# Battery.net
KiCad netlist of a schematic drawn in Altium Designer
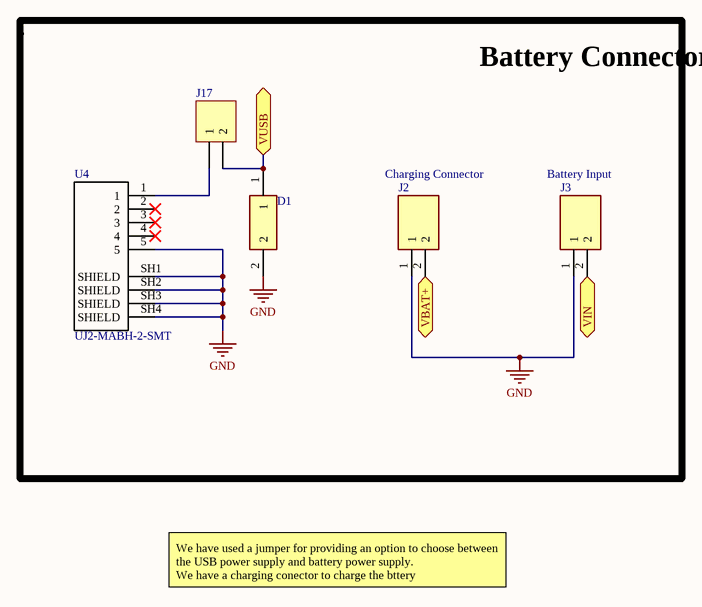
[diagram p0: Battery.SchDoc]

(export (version "E")
  (design (tool "Eeschema 10.0.6"))
  (components
    (comp (ref "D1")
      (value "TPD1E10B06DPYT")
      (footprint "Library_Cart:DPY(R-PX1SON-N2)")
      (description "TVS Diode (Bi-directional)")
      (fields (field (name "MOUSER PART NUMBER") "595-TPD1E10B06DPYT"))
      (libsource (lib "*") (part "TPD1E10B06DPYT"))
    )
    (comp (ref "J2")
      (value "282837-2")
      (footprint "SamacSys:SHDR2W100P0X508_1X2_1016X820X1030P")
      (description "Connector")
      (fields (field (name "MOUSER PART NUMBER") "571-2828372") (field (name "RS PART NUMBER") "7100100P"))
      (libsource (lib "*") (part "282837-2"))
    )
    (comp (ref "J3")
      (value "282837-2")
      (footprint "SamacSys:SHDR2W100P0X508_1X2_1016X820X1030P")
      (description "Connector")
      (fields (field (name "MOUSER PART NUMBER") "571-2828372") (field (name "RS PART NUMBER") "7100100P"))
      (libsource (lib "*") (part "282837-2"))
    )
    (comp (ref "J17")
      (value "Header 2")
      (footprint "HDR1X2")
      (description "Header, 2-Pin")
      (fields
        (field (name "MANUFACTURER_PART_NUMBER") "BG301-04-A-0540-L-B")
        (field (name "DIGI-KEY PART NUMBER") "2073-BG301-02-A-0540-L-BCT-ND")
      )
      (libsource (lib "Miscellaneous Connectors") (part "Header 2"))
    )
    (comp (ref "U4")
      (value "UJ2-MABH-2-SMT")
      (footprint "*CUI_UJ2-MABH-2-SMT_UJ2-MABH-2-SMT(Primary)")
      (description "Mini AB, USB 2.0, 1 A, Right Angle, Surface Mount _SMT_, USB Receptacle")
      (fields
        (field (name "MANUFACTURER_PART_NUMBER") "UJ2-MBH-3-SMT-TR")
        (field (name "DIGI-KEY PART NUMBER") "102-5891-1-ND")
      )
      (libsource (lib "UJ2-MABH-2-SMT") (part "UJ2-MABH-2-SMT"))
    )
  )
  (nets
    (net (code "1") (name "/VBAT+") (class "Default")
      (node (ref "J2") (pin "2") (pinfunction "2_2") (pintype "passive"))
    )
    (net (code "2") (name "/VIN") (class "Default")
      (node (ref "J3") (pin "2") (pinfunction "2_2") (pintype "passive"))
    )
    (net (code "3") (name "/VUSB") (class "Default")
      (node (ref "D1") (pin "1") (pinfunction "1_1") (pintype "passive"))
      (node (ref "J17") (pin "2") (pinfunction "2_2") (pintype "passive"))
    )
    (net (code "4") (name "GND") (class "Default")
      (node (ref "D1") (pin "2") (pinfunction "2_2") (pintype "passive"))
      (node (ref "J2") (pin "1") (pinfunction "1_1") (pintype "passive"))
      (node (ref "J3") (pin "1") (pinfunction "1_1") (pintype "passive"))
      (node (ref "U4") (pin "5") (pinfunction "5_5") (pintype "passive"))
      (node (ref "U4") (pin "SH1") (pinfunction "SHIELD_SH1") (pintype "passive"))
      (node (ref "U4") (pin "SH2") (pinfunction "SHIELD_SH2") (pintype "passive"))
      (node (ref "U4") (pin "SH3") (pinfunction "SHIELD_SH3") (pintype "passive"))
      (node (ref "U4") (pin "SH4") (pinfunction "SHIELD_SH4") (pintype "passive"))
    )
    (net (code "5") (name "Net-(J17-Pad1)") (class "Default")
      (node (ref "J17") (pin "1") (pinfunction "1_1") (pintype "passive"))
      (node (ref "U4") (pin "1") (pinfunction "1_1") (pintype "passive"))
    )
    (net (code "6") (name "unconnected-(U4-Pad2)") (class "Default")
      (node (ref "U4") (pin "2") (pinfunction "2_2") (pintype "passive+no_connect"))
    )
    (net (code "7") (name "unconnected-(U4-Pad3)") (class "Default")
      (node (ref "U4") (pin "3") (pinfunction "3_3") (pintype "passive+no_connect"))
    )
    (net (code "8") (name "unconnected-(U4-Pad4)") (class "Default")
      (node (ref "U4") (pin "4") (pinfunction "4_4") (pintype "passive+no_connect"))
    )
  )
)
